# sensor_board_v0_52.net
KiCad netlist of a schematic drawn in EAGLE
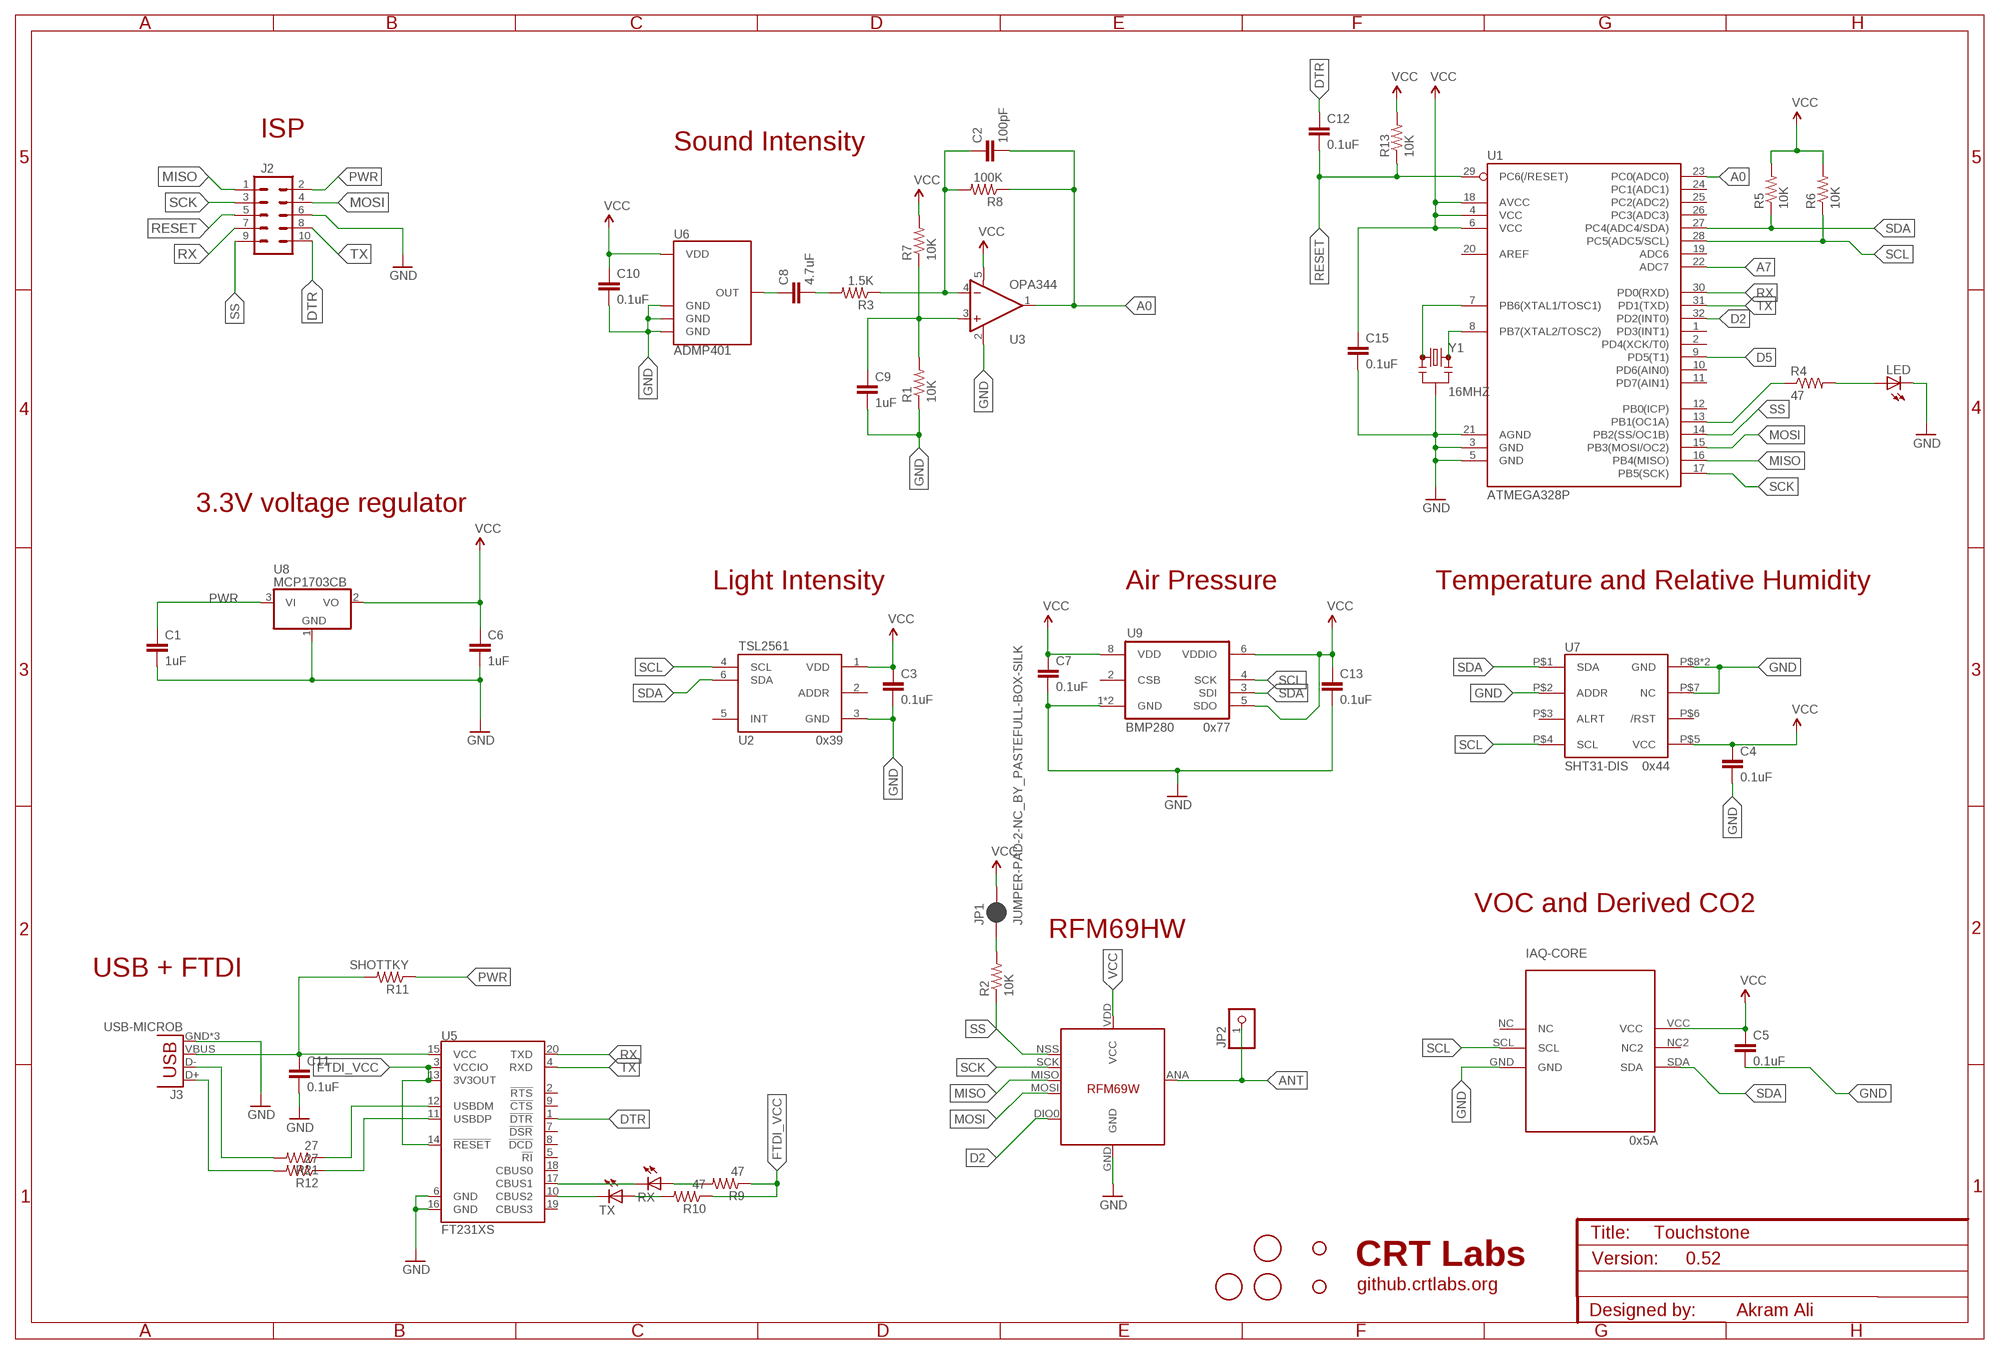
[diagram p0: schematic, sheet 1]

(export (version "E")
  (design (tool "Eeschema 10.0.6"))
  (components
    (comp (ref "C1")
      (value "1uF")
      (footprint "eagle-import:0805")
      (libsource (lib "eagle-import") (part "CAP0805"))
    )
    (comp (ref "C2")
      (value "100pF")
      (footprint "eagle-import:0805")
      (libsource (lib "eagle-import") (part "CAP0805"))
    )
    (comp (ref "C3")
      (value "0.1uF")
      (footprint "eagle-import:0805")
      (libsource (lib "eagle-import") (part "SparkFun-Passives_CAP0805"))
    )
    (comp (ref "C4")
      (value "0.1uF")
      (footprint "eagle-import:0805")
      (libsource (lib "eagle-import") (part "SparkFun-Passives_CAP0805"))
    )
    (comp (ref "C5")
      (value "0.1uF")
      (footprint "eagle-import:0805")
      (libsource (lib "eagle-import") (part "SparkFun-Passives_CAP0805"))
    )
    (comp (ref "C6")
      (value "1uF")
      (footprint "eagle-import:0805")
      (libsource (lib "eagle-import") (part "CAP0805"))
    )
    (comp (ref "C7")
      (value "0.1uF")
      (footprint "eagle-import:0805")
      (libsource (lib "eagle-import") (part "SparkFun-Passives_CAP0805"))
    )
    (comp (ref "C8")
      (value "4.7uF")
      (footprint "eagle-import:0805")
      (libsource (lib "eagle-import") (part "CAP0805"))
    )
    (comp (ref "C9")
      (value "1uF")
      (footprint "eagle-import:0805")
      (libsource (lib "eagle-import") (part "CAP0805"))
    )
    (comp (ref "C10")
      (value "0.1uF")
      (footprint "eagle-import:0805")
      (libsource (lib "eagle-import") (part "CAP0805"))
    )
    (comp (ref "C11")
      (value "0.1uF")
      (footprint "eagle-import:0805")
      (libsource (lib "eagle-import") (part "CAP0805"))
    )
    (comp (ref "C12")
      (value "0.1uF")
      (footprint "eagle-import:0805")
      (libsource (lib "eagle-import") (part "SparkFun-Passives_CAP0805"))
    )
    (comp (ref "C13")
      (value "0.1uF")
      (footprint "eagle-import:0805")
      (libsource (lib "eagle-import") (part "SparkFun-Passives_CAP0805"))
    )
    (comp (ref "C15")
      (value "0.1uF")
      (footprint "eagle-import:0805")
      (libsource (lib "eagle-import") (part "SparkFun-Passives_CAP0805"))
    )
    (comp (ref "H1")
      (value "STAND-OFF")
      (footprint "eagle-import:STAND-OFF")
      (libsource (lib "eagle-import") (part "STAND-OFF"))
    )
    (comp (ref "H2")
      (value "STAND-OFF")
      (footprint "eagle-import:STAND-OFF")
      (libsource (lib "eagle-import") (part "STAND-OFF"))
    )
    (comp (ref "IAQ-CORE")
      (value "IAQ-CORE")
      (footprint "eagle-import:IAQ-CORE")
      (fields (field (name "MPN") "IAQ CORE"))
      (libsource (lib "eagle-import") (part "IAQ-CORE"))
    )
    (comp (ref "J2")
      (value "M05X2PTH")
      (footprint "eagle-import:AVR_ICSP")
      (libsource (lib "eagle-import") (part "M05X2PTH"))
    )
    (comp (ref "J3")
      (value "USB-MICROB")
      (footprint "eagle-import:USB-MICROB")
      (libsource (lib "eagle-import") (part "USB-MICROB"))
    )
    (comp (ref "JP1")
      (value "JUMPER-PAD-2-NC_BY_PASTEFULL-BOX-SILK")
      (footprint "eagle-import:PAD-JUMPER-2-NC_BY_PASTE_YES_SILK_FULL_BOX")
      (libsource (lib "eagle-import") (part "JUMPER-PAD-2-NC_BY_PASTEFULL-BOX-SILK"))
    )
    (comp (ref "JP2")
      (value "PINHD-1X1")
      (footprint "eagle-import:1X01")
      (libsource (lib "eagle-import") (part "PINHD-1X1"))
    )
    (comp (ref "LED")
      (value "LEDCHIPLED_0805")
      (footprint "eagle-import:CHIPLED_0805")
      (libsource (lib "eagle-import") (part "LEDCHIPLED_0805"))
    )
    (comp (ref "R1")
      (value "10K")
      (footprint "eagle-import:0805")
      (libsource (lib "eagle-import") (part "RESISTOR0805-RES"))
    )
    (comp (ref "R2")
      (value "10K")
      (footprint "eagle-import:0805")
      (libsource (lib "eagle-import") (part "RESISTOR0805-RES"))
    )
    (comp (ref "R3")
      (value "1.5K")
      (footprint "eagle-import:0805")
      (libsource (lib "eagle-import") (part "RESISTOR0805-RES"))
    )
    (comp (ref "R4")
      (value "47")
      (footprint "eagle-import:0805")
      (libsource (lib "eagle-import") (part "SparkFun-Resistors_RESISTOR0805-RES"))
    )
    (comp (ref "R5")
      (value "10K")
      (footprint "eagle-import:0805")
      (libsource (lib "eagle-import") (part "SparkFun-Resistors_RESISTOR0805-RES"))
    )
    (comp (ref "R6")
      (value "10K")
      (footprint "eagle-import:0805")
      (libsource (lib "eagle-import") (part "SparkFun-Resistors_RESISTOR0805-RES"))
    )
    (comp (ref "R7")
      (value "10K")
      (footprint "eagle-import:0805")
      (libsource (lib "eagle-import") (part "RESISTOR0805-RES"))
    )
    (comp (ref "R8")
      (value "100K")
      (footprint "eagle-import:0805")
      (libsource (lib "eagle-import") (part "RESISTOR0805-RES"))
    )
    (comp (ref "R9")
      (value "47")
      (footprint "eagle-import:0805")
      (libsource (lib "eagle-import") (part "RESISTOR0805-RES"))
    )
    (comp (ref "R10")
      (value "47")
      (footprint "eagle-import:0805")
      (libsource (lib "eagle-import") (part "RESISTOR0805-RES"))
    )
    (comp (ref "R11")
      (value "SHOTTKY")
      (footprint "eagle-import:0805")
      (libsource (lib "eagle-import") (part "RESISTOR0805-RES"))
    )
    (comp (ref "R12")
      (value "27")
      (footprint "eagle-import:0805")
      (libsource (lib "eagle-import") (part "RESISTOR0805-RES"))
    )
    (comp (ref "R13")
      (value "10K")
      (footprint "eagle-import:0805")
      (libsource (lib "eagle-import") (part "RESISTOR0805-RES"))
    )
    (comp (ref "R21")
      (value "27")
      (footprint "eagle-import:0805")
      (libsource (lib "eagle-import") (part "RESISTOR0805-RES"))
    )
    (comp (ref "RX")
      (value "LEDCHIPLED_0805")
      (footprint "eagle-import:CHIPLED_0805")
      (libsource (lib "eagle-import") (part "LEDCHIPLED_0805"))
    )
    (comp (ref "TX")
      (value "LEDCHIPLED_0805")
      (footprint "eagle-import:CHIPLED_0805")
      (libsource (lib "eagle-import") (part "LEDCHIPLED_0805"))
    )
    (comp (ref "U$1")
      (value "FIDUCIAL")
      (footprint "eagle-import:FIDUCIAL_1MM")
      (libsource (lib "eagle-import") (part "FIDUCIAL"))
    )
    (comp (ref "U$2")
      (value "FIDUCIAL")
      (footprint "eagle-import:FIDUCIAL_1MM")
      (libsource (lib "eagle-import") (part "FIDUCIAL"))
    )
    (comp (ref "U$3")
      (value "FIDUCIAL")
      (footprint "eagle-import:FIDUCIAL_1MM")
      (libsource (lib "eagle-import") (part "FIDUCIAL"))
    )
    (comp (ref "U1")
      (value "ATMEGA328P")
      (footprint "eagle-import:TQFP32-08")
      (fields (field (name "MPN") "ATMEGA328PB-AU"))
      (libsource (lib "eagle-import") (part "ATMEGA328P_TQFP"))
    )
    (comp (ref "U2")
      (value "TSL2561")
      (footprint "eagle-import:FN-6")
      (fields (field (name "MANF") "AMS-TAOS-USA-Inc.") (field (name "MPN") "TSL2561FN"))
      (libsource (lib "eagle-import") (part "TSL2561FN"))
    )
    (comp (ref "U3")
      (value "OPA344")
      (footprint "eagle-import:SOT23-5")
      (libsource (lib "eagle-import") (part "OPA344"))
    )
    (comp (ref "U4")
      (value "RFM69HW")
      (footprint "eagle-import:LOWPOWERLAB_RFM69W-MINPADS")
      (libsource (lib "eagle-import") (part "LOWPOWERLAB_RFM69"))
    )
    (comp (ref "U5")
      (value "FT231XS")
      (footprint "eagle-import:SSOP20_L")
      (libsource (lib "eagle-import") (part "FT231XS"))
    )
    (comp (ref "U6")
      (value "ADMP401")
      (footprint "eagle-import:ADMP401")
      (libsource (lib "eagle-import") (part "ADMP401"))
    )
    (comp (ref "U7")
      (value "SHT31-DIS")
      (footprint "eagle-import:SHT3X")
      (fields (field (name "MPN") "SHT31-DIS-B"))
      (libsource (lib "eagle-import") (part "SHT31-DIS"))
    )
    (comp (ref "U8")
      (value "MCP1703CB")
      (footprint "eagle-import:SOT23")
      (fields (field (name "MPN") "MCP1703T-2502E/CB"))
      (libsource (lib "eagle-import") (part "MCP1703CB"))
    )
    (comp (ref "U9")
      (value "BMP280")
      (footprint "eagle-import:BMP280")
      (libsource (lib "eagle-import") (part "BMP280"))
    )
    (comp (ref "Y1")
      (value "16MHZ")
      (footprint "eagle-import:RESONATOR-SMD")
      (libsource (lib "eagle-import") (part "RESONATOR16MHZ"))
    )
  )
  (nets
    (net (code "1") (name "A0") (class "Default")
      (node (ref "C2") (pin "2") (pinfunction "2_2") (pintype "passive"))
      (node (ref "R8") (pin "1") (pinfunction "1_1") (pintype "passive"))
      (node (ref "U1") (pin "23") (pinfunction "PC0(ADC0)_23") (pintype "bidirectional"))
      (node (ref "U3") (pin "1") (pinfunction "OUT_1") (pintype "output"))
    )
    (net (code "2") (name "A7") (class "Default")
      (node (ref "U1") (pin "22") (pinfunction "ADC7_22") (pintype "bidirectional"))
    )
    (net (code "3") (name "ANT") (class "Default")
      (node (ref "JP2") (pin "1") (pinfunction "1_1") (pintype "passive"))
      (node (ref "U4") (pin "ANA") (pinfunction "ANT_ANA") (pintype "passive"))
    )
    (net (code "4") (name "D2") (class "Default")
      (node (ref "U1") (pin "32") (pinfunction "PD2(INT0)_32") (pintype "bidirectional"))
      (node (ref "U4") (pin "DIO0") (pinfunction "DIO0_DIO0") (pintype "open_collector"))
    )
    (net (code "5") (name "D5") (class "Default")
      (node (ref "U1") (pin "9") (pinfunction "PD5(T1)_9") (pintype "bidirectional"))
    )
    (net (code "6") (name "DTR") (class "Default")
      (node (ref "C12") (pin "1") (pinfunction "1_1") (pintype "passive"))
      (node (ref "J2") (pin "10") (pinfunction "10_10") (pintype "passive"))
      (node (ref "U5") (pin "1") (pinfunction "~{DTR}_1") (pintype "bidirectional"))
    )
    (net (code "7") (name "FTDI_VCC") (class "Default")
      (node (ref "R10") (pin "1") (pinfunction "1_1") (pintype "passive"))
      (node (ref "R9") (pin "1") (pinfunction "1_1") (pintype "passive"))
      (node (ref "U5") (pin "13") (pinfunction "3V3OUT_13") (pintype "bidirectional"))
      (node (ref "U5") (pin "14") (pinfunction "~{RESET}_14") (pintype "bidirectional"))
      (node (ref "U5") (pin "3") (pinfunction "VCCIO_3") (pintype "bidirectional"))
    )
    (net (code "8") (name "GND") (class "Default")
      (node (ref "C1") (pin "2") (pinfunction "2_2") (pintype "passive"))
      (node (ref "C10") (pin "2") (pinfunction "2_2") (pintype "passive"))
      (node (ref "C11") (pin "2") (pinfunction "2_2") (pintype "passive"))
      (node (ref "C13") (pin "2") (pinfunction "2_2") (pintype "passive"))
      (node (ref "C15") (pin "2") (pinfunction "2_2") (pintype "passive"))
      (node (ref "C3") (pin "2") (pinfunction "2_2") (pintype "passive"))
      (node (ref "C4") (pin "2") (pinfunction "2_2") (pintype "passive"))
      (node (ref "C5") (pin "2") (pinfunction "2_2") (pintype "passive"))
      (node (ref "C6") (pin "2") (pinfunction "2_2") (pintype "passive"))
      (node (ref "C7") (pin "2") (pinfunction "2_2") (pintype "passive"))
      (node (ref "C9") (pin "2") (pinfunction "2_2") (pintype "passive"))
      (node (ref "IAQ-CORE") (pin "GND") (pinfunction "GND_GND") (pintype "bidirectional"))
      (node (ref "J2") (pin "6") (pinfunction "6_6") (pintype "passive"))
      (node (ref "J3") (pin "GND") (pinfunction "GND_GND") (pintype "bidirectional"))
      (node (ref "J3") (pin "MT1") (pinfunction "GND_MT1") (pintype "bidirectional"))
      (node (ref "J3") (pin "MT2") (pinfunction "GND_MT2") (pintype "bidirectional"))
      (node (ref "LED") (pin "C") (pinfunction "C_C") (pintype "passive"))
      (node (ref "R1") (pin "1") (pinfunction "1_1") (pintype "passive"))
      (node (ref "U1") (pin "21") (pinfunction "AGND_21") (pintype "bidirectional"))
      (node (ref "U1") (pin "3") (pinfunction "GND_3") (pintype "bidirectional"))
      (node (ref "U1") (pin "5") (pinfunction "GND_5") (pintype "bidirectional"))
      (node (ref "U2") (pin "3") (pinfunction "GND_3") (pintype "power_in"))
      (node (ref "U3") (pin "2") (pinfunction "V-_2") (pintype "power_in"))
      (node (ref "U4") (pin "GND") (pinfunction "GND_GND") (pintype "power_in"))
      (node (ref "U5") (pin "16") (pinfunction "GND_16") (pintype "bidirectional"))
      (node (ref "U5") (pin "6") (pinfunction "GND_6") (pintype "bidirectional"))
      (node (ref "U6") (pin "2") (pinfunction "GND_2") (pintype "bidirectional"))
      (node (ref "U6") (pin "4") (pinfunction "GND_4") (pintype "bidirectional"))
      (node (ref "U6") (pin "6") (pinfunction "GND_6") (pintype "bidirectional"))
      (node (ref "U7") (pin "P$2") (pinfunction "ADDR_P$2") (pintype "bidirectional"))
      (node (ref "U7") (pin "P$7") (pinfunction "NC_P$7") (pintype "bidirectional"))
      (node (ref "U7") (pin "P$8") (pinfunction "GND_P$8") (pintype "bidirectional"))
      (node (ref "U7") (pin "PAD") (pinfunction "GND_PAD") (pintype "bidirectional"))
      (node (ref "U8") (pin "1") (pinfunction "GND_1") (pintype "passive"))
      (node (ref "U9") (pin "1") (pinfunction "GND_1") (pintype "power_in"))
      (node (ref "U9") (pin "7") (pinfunction "GND_7") (pintype "power_in"))
      (node (ref "Y1") (pin "2") (pinfunction "2_2") (pintype "passive"))
    )
    (net (code "9") (name "MISO") (class "Default")
      (node (ref "J2") (pin "1") (pinfunction "1_1") (pintype "passive"))
      (node (ref "U1") (pin "16") (pinfunction "PB4(MISO)_16") (pintype "bidirectional"))
      (node (ref "U4") (pin "MISO") (pinfunction "MISO_MISO") (pintype "input"))
    )
    (net (code "10") (name "MOSI") (class "Default")
      (node (ref "J2") (pin "4") (pinfunction "4_4") (pintype "passive"))
      (node (ref "U1") (pin "15") (pinfunction "PB3(MOSI/OC2)_15") (pintype "bidirectional"))
      (node (ref "U4") (pin "MOSI") (pinfunction "MOSI_MOSI") (pintype "output"))
    )
    (net (code "11") (name "Net-(C8-Pad2)") (class "Default")
      (node (ref "C8") (pin "2") (pinfunction "2_2") (pintype "passive"))
      (node (ref "R3") (pin "2") (pinfunction "2_2") (pintype "passive"))
    )
    (net (code "12") (name "Net-(J3-PadD+)") (class "Default")
      (node (ref "J3") (pin "D+") (pinfunction "D+_D+") (pintype "bidirectional"))
      (node (ref "R12") (pin "2") (pinfunction "2_2") (pintype "passive"))
    )
    (net (code "13") (name "Net-(J3-PadD-)") (class "Default")
      (node (ref "J3") (pin "D-") (pinfunction "D-_D-") (pintype "bidirectional"))
      (node (ref "R21") (pin "2") (pinfunction "2_2") (pintype "passive"))
    )
    (net (code "14") (name "Net-(JP1-Pad1)") (class "Default")
      (node (ref "JP1") (pin "1") (pinfunction "1_1") (pintype "passive"))
      (node (ref "R2") (pin "2") (pinfunction "2_2") (pintype "passive"))
    )
    (net (code "15") (name "Net-(LED-PadA)") (class "Default")
      (node (ref "LED") (pin "A") (pinfunction "A_A") (pintype "passive"))
      (node (ref "R4") (pin "2") (pinfunction "2_2") (pintype "passive"))
    )
    (net (code "16") (name "Net-(R9-Pad2)") (class "Default")
      (node (ref "R9") (pin "2") (pinfunction "2_2") (pintype "passive"))
      (node (ref "RX") (pin "A") (pinfunction "A_A") (pintype "passive"))
    )
    (net (code "17") (name "Net-(R10-Pad2)") (class "Default")
      (node (ref "R10") (pin "2") (pinfunction "2_2") (pintype "passive"))
      (node (ref "TX") (pin "A") (pinfunction "A_A") (pintype "passive"))
    )
    (net (code "18") (name "Net-(U1-PB1(OC1A))") (class "Default")
      (node (ref "R4") (pin "1") (pinfunction "1_1") (pintype "passive"))
      (node (ref "U1") (pin "13") (pinfunction "PB1(OC1A)_13") (pintype "bidirectional"))
    )
    (net (code "19") (name "Net-(U1-PB6(XTAL1{slash}TOSC1))") (class "Default")
      (node (ref "U1") (pin "7") (pinfunction "PB6(XTAL1/TOSC1)_7") (pintype "bidirectional"))
      (node (ref "Y1") (pin "1") (pinfunction "1_1") (pintype "passive"))
    )
    (net (code "20") (name "Net-(U1-PB7(XTAL2{slash}TOSC2))") (class "Default")
      (node (ref "U1") (pin "8") (pinfunction "PB7(XTAL2/TOSC2)_8") (pintype "bidirectional"))
      (node (ref "Y1") (pin "3") (pinfunction "3_3") (pintype "passive"))
    )
    (net (code "21") (name "Net-(U3-+IN)") (class "Default")
      (node (ref "C9") (pin "1") (pinfunction "1_1") (pintype "passive"))
      (node (ref "R1") (pin "2") (pinfunction "2_2") (pintype "passive"))
      (node (ref "R7") (pin "1") (pinfunction "1_1") (pintype "passive"))
      (node (ref "U3") (pin "3") (pinfunction "+IN_3") (pintype "input"))
    )
    (net (code "22") (name "Net-(U3--IN)") (class "Default")
      (node (ref "C2") (pin "1") (pinfunction "1_1") (pintype "passive"))
      (node (ref "R3") (pin "1") (pinfunction "1_1") (pintype "passive"))
      (node (ref "R8") (pin "2") (pinfunction "2_2") (pintype "passive"))
      (node (ref "U3") (pin "4") (pinfunction "-IN_4") (pintype "input"))
    )
    (net (code "23") (name "Net-(U5-CBUS1)") (class "Default")
      (node (ref "RX") (pin "C") (pinfunction "C_C") (pintype "passive"))
      (node (ref "U5") (pin "17") (pinfunction "CBUS1_17") (pintype "bidirectional"))
    )
    (net (code "24") (name "Net-(U5-CBUS2)") (class "Default")
      (node (ref "TX") (pin "C") (pinfunction "C_C") (pintype "passive"))
      (node (ref "U5") (pin "10") (pinfunction "CBUS2_10") (pintype "bidirectional"))
    )
    (net (code "25") (name "Net-(U5-USBDM)") (class "Default")
      (node (ref "R21") (pin "1") (pinfunction "1_1") (pintype "passive"))
      (node (ref "U5") (pin "12") (pinfunction "USBDM_12") (pintype "bidirectional"))
    )
    (net (code "26") (name "Net-(U5-USBDP)") (class "Default")
      (node (ref "R12") (pin "1") (pinfunction "1_1") (pintype "passive"))
      (node (ref "U5") (pin "11") (pinfunction "USBDP_11") (pintype "bidirectional"))
    )
    (net (code "27") (name "Net-(U5-VCC)") (class "Default")
      (node (ref "C11") (pin "1") (pinfunction "1_1") (pintype "passive"))
      (node (ref "J3") (pin "VBUS") (pinfunction "VBUS_VBUS") (pintype "bidirectional"))
      (node (ref "R11") (pin "2") (pinfunction "2_2") (pintype "passive"))
      (node (ref "U5") (pin "15") (pinfunction "VCC_15") (pintype "bidirectional"))
    )
    (net (code "28") (name "Net-(U6-OUT)") (class "Default")
      (node (ref "C8") (pin "1") (pinfunction "1_1") (pintype "passive"))
      (node (ref "U6") (pin "1") (pinfunction "OUT_1") (pintype "bidirectional"))
    )
    (net (code "29") (name "PWR") (class "Default")
      (node (ref "C1") (pin "1") (pinfunction "1_1") (pintype "passive"))
      (node (ref "J2") (pin "2") (pinfunction "2_2") (pintype "passive"))
      (node (ref "R11") (pin "1") (pinfunction "1_1") (pintype "passive"))
      (node (ref "U8") (pin "3") (pinfunction "VI_3") (pintype "input"))
    )
    (net (code "30") (name "RESET") (class "Default")
      (node (ref "C12") (pin "2") (pinfunction "2_2") (pintype "passive"))
      (node (ref "J2") (pin "5") (pinfunction "5_5") (pintype "passive"))
      (node (ref "R13") (pin "1") (pinfunction "1_1") (pintype "passive"))
      (node (ref "U1") (pin "29") (pinfunction "PC6(/RESET)_29") (pintype "bidirectional"))
    )
    (net (code "31") (name "RX") (class "Default")
      (node (ref "J2") (pin "7") (pinfunction "7_7") (pintype "passive"))
      (node (ref "U1") (pin "30") (pinfunction "PD0(RXD)_30") (pintype "bidirectional"))
      (node (ref "U5") (pin "20") (pinfunction "TXD_20") (pintype "bidirectional"))
    )
    (net (code "32") (name "SCK") (class "Default")
      (node (ref "J2") (pin "3") (pinfunction "3_3") (pintype "passive"))
      (node (ref "U1") (pin "17") (pinfunction "PB5(SCK)_17") (pintype "bidirectional"))
      (node (ref "U4") (pin "SCK") (pinfunction "SCK_SCK") (pintype "input"))
    )
    (net (code "33") (name "SCL") (class "Default")
      (node (ref "IAQ-CORE") (pin "SCL") (pinfunction "SCL_SCL") (pintype "bidirectional"))
      (node (ref "R6") (pin "1") (pinfunction "1_1") (pintype "passive"))
      (node (ref "U1") (pin "28") (pinfunction "PC5(ADC5/SCL)_28") (pintype "bidirectional"))
      (node (ref "U2") (pin "4") (pinfunction "SCL_4") (pintype "input"))
      (node (ref "U7") (pin "P$4") (pinfunction "SCL_P$4") (pintype "bidirectional"))
      (node (ref "U9") (pin "4") (pinfunction "SCK_4") (pintype "bidirectional"))
    )
    (net (code "34") (name "SDA") (class "Default")
      (node (ref "IAQ-CORE") (pin "SDA") (pinfunction "SDA_SDA") (pintype "bidirectional"))
      (node (ref "R5") (pin "1") (pinfunction "1_1") (pintype "passive"))
      (node (ref "U1") (pin "27") (pinfunction "PC4(ADC4/SDA)_27") (pintype "bidirectional"))
      (node (ref "U2") (pin "6") (pinfunction "SDA_6") (pintype "bidirectional"))
      (node (ref "U7") (pin "P$1") (pinfunction "SDA_P$1") (pintype "bidirectional"))
      (node (ref "U9") (pin "3") (pinfunction "SDI_3") (pintype "bidirectional"))
    )
    (net (code "35") (name "SS") (class "Default")
      (node (ref "J2") (pin "9") (pinfunction "9_9") (pintype "passive"))
      (node (ref "R2") (pin "1") (pinfunction "1_1") (pintype "passive"))
      (node (ref "U1") (pin "14") (pinfunction "PB2(SS/OC1B)_14") (pintype "bidirectional"))
      (node (ref "U4") (pin "NSS") (pinfunction "SEL_NSS") (pintype "input"))
    )
    (net (code "36") (name "TX") (class "Default")
      (node (ref "J2") (pin "8") (pinfunction "8_8") (pintype "passive"))
      (node (ref "U1") (pin "31") (pinfunction "PD1(TXD)_31") (pintype "bidirectional"))
      (node (ref "U5") (pin "4") (pinfunction "RXD_4") (pintype "bidirectional"))
    )
    (net (code "37") (name "VCC") (class "Default")
      (node (ref "C10") (pin "1") (pinfunction "1_1") (pintype "passive"))
      (node (ref "C13") (pin "1") (pinfunction "1_1") (pintype "passive"))
      (node (ref "C15") (pin "1") (pinfunction "1_1") (pintype "passive"))
      (node (ref "C3") (pin "1") (pinfunction "1_1") (pintype "passive"))
      (node (ref "C4") (pin "1") (pinfunction "1_1") (pintype "passive"))
      (node (ref "C5") (pin "1") (pinfunction "1_1") (pintype "passive"))
      (node (ref "C6") (pin "1") (pinfunction "1_1") (pintype "passive"))
      (node (ref "C7") (pin "1") (pinfunction "1_1") (pintype "passive"))
      (node (ref "IAQ-CORE") (pin "VCC") (pinfunction "VCC_VCC") (pintype "bidirectional"))
      (node (ref "JP1") (pin "2") (pinfunction "2_2") (pintype "passive"))
      (node (ref "R13") (pin "2") (pinfunction "2_2") (pintype "passive"))
      (node (ref "R5") (pin "2") (pinfunction "2_2") (pintype "passive"))
      (node (ref "R6") (pin "2") (pinfunction "2_2") (pintype "passive"))
      (node (ref "R7") (pin "2") (pinfunction "2_2") (pintype "passive"))
      (node (ref "U1") (pin "18") (pinfunction "AVCC_18") (pintype "bidirectional"))
      (node (ref "U1") (pin "4") (pinfunction "VCC_4") (pintype "bidirectional"))
      (node (ref "U1") (pin "6") (pinfunction "VCC_6") (pintype "bidirectional"))
      (node (ref "U2") (pin "1") (pinfunction "VDD_1") (pintype "power_in"))
      (node (ref "U3") (pin "5") (pinfunction "V+_5") (pintype "power_in"))
      (node (ref "U4") (pin "VDD") (pinfunction "VCC_VDD") (pintype "power_in"))
      (node (ref "U6") (pin "5") (pinfunction "VDD_5") (pintype "bidirectional"))
      (node (ref "U7") (pin "P$5") (pinfunction "VCC_P$5") (pintype "bidirectional"))
      (node (ref "U8") (pin "2") (pinfunction "VO_2") (pintype "passive"))
      (node (ref "U9") (pin "5") (pinfunction "SDO_5") (pintype "input"))
      (node (ref "U9") (pin "6") (pinfunction "VDDIO_6") (pintype "power_in"))
      (node (ref "U9") (pin "8") (pinfunction "VDD_8") (pintype "power_in"))
    )
    (net (code "38") (name "unconnected-(IAQ-CORE-PadNC)") (class "Default")
      (node (ref "IAQ-CORE") (pin "NC") (pinfunction "NC_NC") (pintype "bidirectional"))
    )
    (net (code "39") (name "unconnected-(IAQ-CORE-PadNC2)") (class "Default")
      (node (ref "IAQ-CORE") (pin "NC2") (pinfunction "NC2_NC2") (pintype "bidirectional"))
    )
    (net (code "40") (name "unconnected-(U1-ADC6-Pad19)") (class "Default")
      (node (ref "U1") (pin "19") (pinfunction "ADC6_19") (pintype "bidirectional"))
    )
    (net (code "41") (name "unconnected-(U1-AREF-Pad20)") (class "Default")
      (node (ref "U1") (pin "20") (pinfunction "AREF_20") (pintype "bidirectional"))
    )
    (net (code "42") (name "unconnected-(U1-PB0(ICP)-Pad12)") (class "Default")
      (node (ref "U1") (pin "12") (pinfunction "PB0(ICP)_12") (pintype "bidirectional"))
    )
    (net (code "43") (name "unconnected-(U1-PC1(ADC1)-Pad24)") (class "Default")
      (node (ref "U1") (pin "24") (pinfunction "PC1(ADC1)_24") (pintype "bidirectional"))
    )
    (net (code "44") (name "unconnected-(U1-PC2(ADC2)-Pad25)") (class "Default")
      (node (ref "U1") (pin "25") (pinfunction "PC2(ADC2)_25") (pintype "bidirectional"))
    )
    (net (code "45") (name "unconnected-(U1-PC3(ADC3)-Pad26)") (class "Default")
      (node (ref "U1") (pin "26") (pinfunction "PC3(ADC3)_26") (pintype "bidirectional"))
    )
    (net (code "46") (name "unconnected-(U1-PD3(INT1)-Pad1)") (class "Default")
      (node (ref "U1") (pin "1") (pinfunction "PD3(INT1)_1") (pintype "bidirectional"))
    )
    (net (code "47") (name "unconnected-(U1-PD4(XCK{slash}T0)-Pad2)") (class "Default")
      (node (ref "U1") (pin "2") (pinfunction "PD4(XCK/T0)_2") (pintype "bidirectional"))
    )
    (net (code "48") (name "unconnected-(U1-PD6(AIN0)-Pad10)") (class "Default")
      (node (ref "U1") (pin "10") (pinfunction "PD6(AIN0)_10") (pintype "bidirectional"))
    )
    (net (code "49") (name "unconnected-(U1-PD7(AIN1)-Pad11)") (class "Default")
      (node (ref "U1") (pin "11") (pinfunction "PD7(AIN1)_11") (pintype "bidirectional"))
    )
    (net (code "50") (name "unconnected-(U2-ADDR-Pad2)") (class "Default")
      (node (ref "U2") (pin "2") (pinfunction "ADDR_2") (pintype "input"))
    )
    (net (code "51") (name "unconnected-(U2-INT-Pad5)") (class "Default")
      (node (ref "U2") (pin "5") (pinfunction "INT_5") (pintype "output"))
    )
    (net (code "52") (name "unconnected-(U5-CBUS0-Pad18)") (class "Default")
      (node (ref "U5") (pin "18") (pinfunction "CBUS0_18") (pintype "bidirectional"))
    )
    (net (code "53") (name "unconnected-(U5-CBUS3-Pad19)") (class "Default")
      (node (ref "U5") (pin "19") (pinfunction "CBUS3_19") (pintype "bidirectional"))
    )
    (net (code "54") (name "unconnected-(U5-~{CTS}-Pad9)") (class "Default")
      (node (ref "U5") (pin "9") (pinfunction "~{CTS}_9") (pintype "bidirectional"))
    )
    (net (code "55") (name "unconnected-(U5-~{DCD}-Pad8)") (class "Default")
      (node (ref "U5") (pin "8") (pinfunction "~{DCD}_8") (pintype "bidirectional"))
    )
    (net (code "56") (name "unconnected-(U5-~{DSR}-Pad7)") (class "Default")
      (node (ref "U5") (pin "7") (pinfunction "~{DSR}_7") (pintype "bidirectional"))
    )
    (net (code "57") (name "unconnected-(U5-~{RI}-Pad5)") (class "Default")
      (node (ref "U5") (pin "5") (pinfunction "~{RI}_5") (pintype "bidirectional"))
    )
    (net (code "58") (name "unconnected-(U5-~{RTS}-Pad2)") (class "Default")
      (node (ref "U5") (pin "2") (pinfunction "~{RTS}_2") (pintype "bidirectional"))
    )
    (net (code "59") (name "unconnected-(U7-ALRT-PadP$3)") (class "Default")
      (node (ref "U7") (pin "P$3") (pinfunction "ALRT_P$3") (pintype "bidirectional"))
    )
    (net (code "60") (name "unconnected-(U7-{slash}RST-PadP$6)") (class "Default")
      (node (ref "U7") (pin "P$6") (pinfunction "/RST_P$6") (pintype "bidirectional"))
    )
    (net (code "61") (name "unconnected-(U9-CSB-Pad2)") (class "Default")
      (node (ref "U9") (pin "2") (pinfunction "CSB_2") (pintype "input"))
    )
  )
)
